# 2_FPGA.net
KiCad netlist of a schematic drawn in Altium Designer
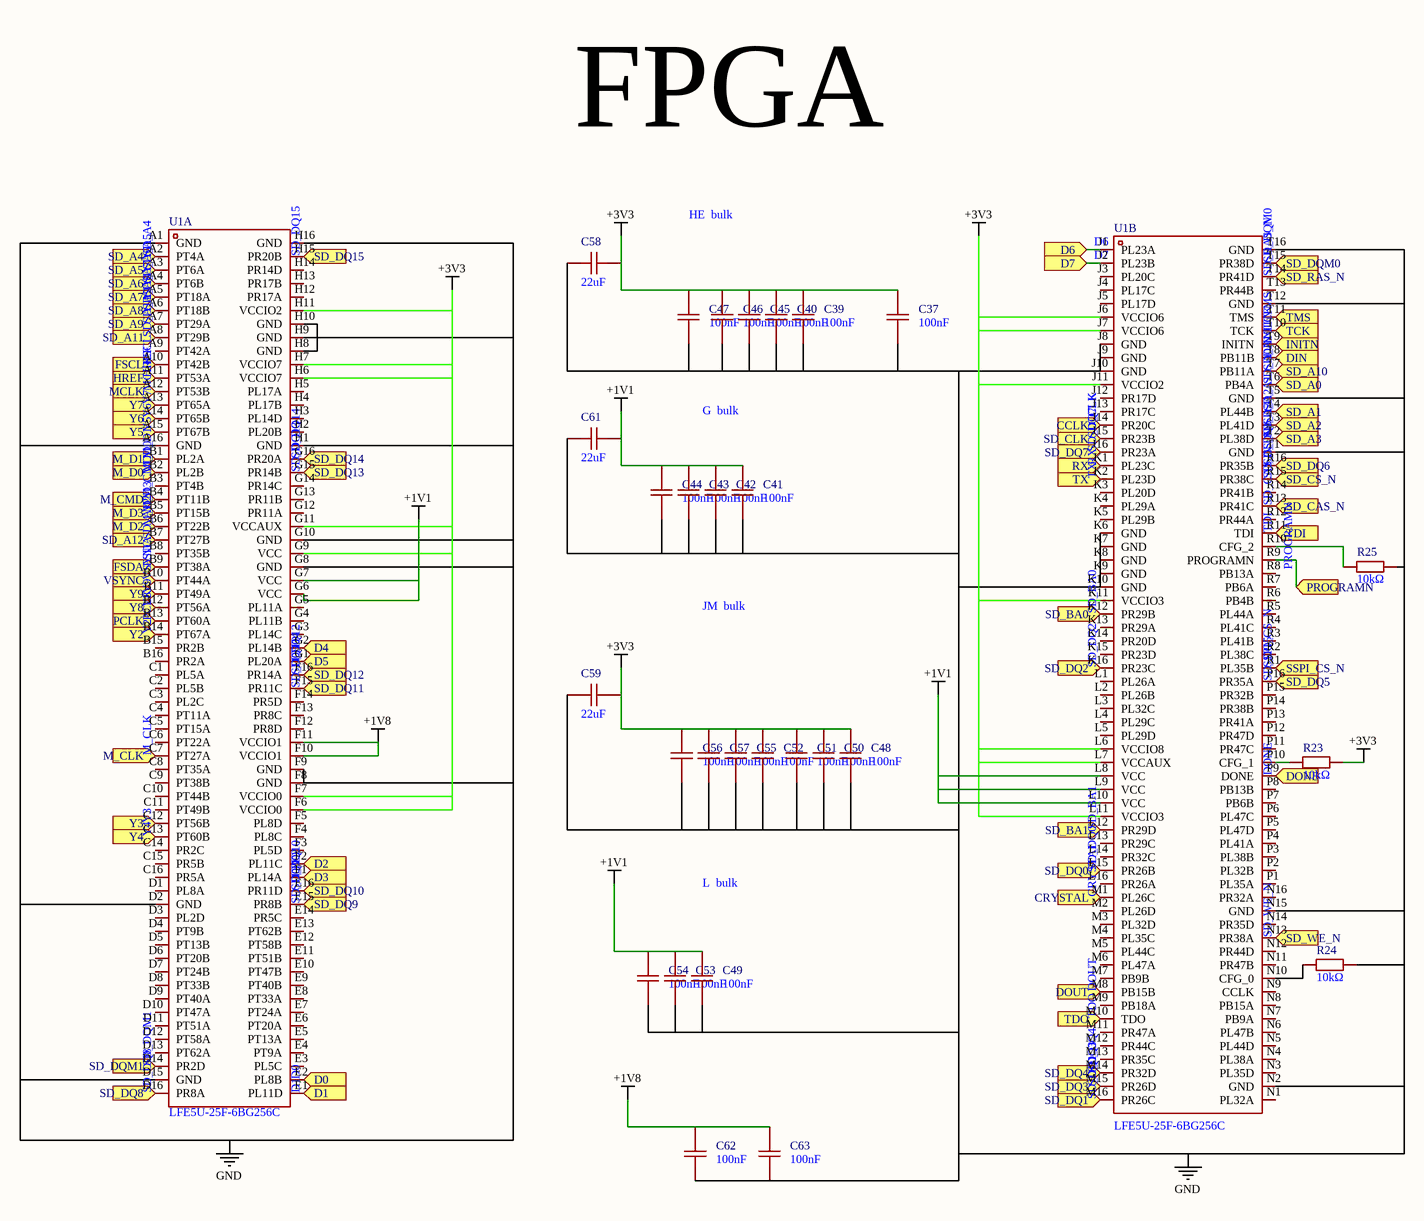
[diagram p0: 2_FPGA.schdoc]

(export (version "E")
  (design (tool "Eeschema 10.0.6"))
  (components
    (comp (ref "C37")
      (value "100nF")
      (footprint "C01005")
      (fields
        (field (name "MANUFACTURER") "muRata(村田)")
        (field (name "MANUFACTURER PART") "GRM022R60J104KE15D")
        (field (name "TOLERANCE") "±10%")
      )
      (libsource (lib "altium-import") (part "root_2_GRM022R60J104KE15D_"))
    )
    (comp (ref "C39")
      (value "100nF")
      (footprint "C01005")
      (fields
        (field (name "MANUFACTURER") "muRata(村田)")
        (field (name "MANUFACTURER PART") "GRM022R60J104KE15D")
        (field (name "TOLERANCE") "±10%")
      )
      (libsource (lib "altium-import") (part "root_2_GRM022R60J104KE15D_"))
    )
    (comp (ref "C40")
      (value "100nF")
      (footprint "C01005")
      (fields
        (field (name "MANUFACTURER") "muRata(村田)")
        (field (name "MANUFACTURER PART") "GRM022R60J104KE15D")
        (field (name "TOLERANCE") "±10%")
      )
      (libsource (lib "altium-import") (part "root_2_GRM022R60J104KE15D_"))
    )
    (comp (ref "C41")
      (value "100nF")
      (footprint "C01005")
      (fields
        (field (name "MANUFACTURER") "muRata(村田)")
        (field (name "MANUFACTURER PART") "GRM022R60J104KE15D")
        (field (name "TOLERANCE") "±10%")
      )
      (libsource (lib "altium-import") (part "root_2_GRM022R60J104KE15D_"))
    )
    (comp (ref "C42")
      (value "100nF")
      (footprint "C01005")
      (fields
        (field (name "MANUFACTURER") "muRata(村田)")
        (field (name "MANUFACTURER PART") "GRM022R60J104KE15D")
        (field (name "TOLERANCE") "±10%")
      )
      (libsource (lib "altium-import") (part "root_2_GRM022R60J104KE15D_"))
    )
    (comp (ref "C43")
      (value "100nF")
      (footprint "C01005")
      (fields
        (field (name "MANUFACTURER") "muRata(村田)")
        (field (name "MANUFACTURER PART") "GRM022R60J104KE15D")
        (field (name "TOLERANCE") "±10%")
      )
      (libsource (lib "altium-import") (part "root_2_GRM022R60J104KE15D_"))
    )
    (comp (ref "C44")
      (value "100nF")
      (footprint "C01005")
      (fields
        (field (name "MANUFACTURER") "muRata(村田)")
        (field (name "MANUFACTURER PART") "GRM022R60J104KE15D")
        (field (name "TOLERANCE") "±10%")
      )
      (libsource (lib "altium-import") (part "root_2_GRM022R60J104KE15D_"))
    )
    (comp (ref "C45")
      (value "100nF")
      (footprint "C01005")
      (fields
        (field (name "MANUFACTURER") "muRata(村田)")
        (field (name "MANUFACTURER PART") "GRM022R60J104KE15D")
        (field (name "TOLERANCE") "±10%")
      )
      (libsource (lib "altium-import") (part "root_2_GRM022R60J104KE15D_"))
    )
    (comp (ref "C46")
      (value "100nF")
      (footprint "C01005")
      (fields
        (field (name "MANUFACTURER") "muRata(村田)")
        (field (name "MANUFACTURER PART") "GRM022R60J104KE15D")
        (field (name "TOLERANCE") "±10%")
      )
      (libsource (lib "altium-import") (part "root_2_GRM022R60J104KE15D_"))
    )
    (comp (ref "C47")
      (value "100nF")
      (footprint "C01005")
      (fields
        (field (name "MANUFACTURER") "muRata(村田)")
        (field (name "MANUFACTURER PART") "GRM022R60J104KE15D")
        (field (name "TOLERANCE") "±10%")
      )
      (libsource (lib "altium-import") (part "root_2_GRM022R60J104KE15D_"))
    )
    (comp (ref "C48")
      (value "100nF")
      (footprint "C01005")
      (fields
        (field (name "MANUFACTURER") "muRata(村田)")
        (field (name "MANUFACTURER PART") "GRM022R60J104KE15D")
        (field (name "TOLERANCE") "±10%")
      )
      (libsource (lib "altium-import") (part "root_2_GRM022R60J104KE15D_"))
    )
    (comp (ref "C49")
      (value "100nF")
      (footprint "C01005")
      (fields
        (field (name "MANUFACTURER") "muRata(村田)")
        (field (name "MANUFACTURER PART") "GRM022R60J104KE15D")
        (field (name "TOLERANCE") "±10%")
      )
      (libsource (lib "altium-import") (part "root_2_GRM022R60J104KE15D_"))
    )
    (comp (ref "C50")
      (value "100nF")
      (footprint "C01005")
      (fields
        (field (name "MANUFACTURER") "muRata(村田)")
        (field (name "MANUFACTURER PART") "GRM022R60J104KE15D")
        (field (name "TOLERANCE") "±10%")
      )
      (libsource (lib "altium-import") (part "root_2_GRM022R60J104KE15D_"))
    )
    (comp (ref "C51")
      (value "100nF")
      (footprint "C01005")
      (fields
        (field (name "MANUFACTURER") "muRata(村田)")
        (field (name "MANUFACTURER PART") "GRM022R60J104KE15D")
        (field (name "TOLERANCE") "±10%")
      )
      (libsource (lib "altium-import") (part "root_2_GRM022R60J104KE15D_"))
    )
    (comp (ref "C52")
      (value "100nF")
      (footprint "C01005")
      (fields
        (field (name "MANUFACTURER") "muRata(村田)")
        (field (name "MANUFACTURER PART") "GRM022R60J104KE15D")
        (field (name "TOLERANCE") "±10%")
      )
      (libsource (lib "altium-import") (part "root_2_GRM022R60J104KE15D_"))
    )
    (comp (ref "C53")
      (value "100nF")
      (footprint "C01005")
      (fields
        (field (name "MANUFACTURER") "muRata(村田)")
        (field (name "MANUFACTURER PART") "GRM022R60J104KE15D")
        (field (name "TOLERANCE") "±10%")
      )
      (libsource (lib "altium-import") (part "root_2_GRM022R60J104KE15D_"))
    )
    (comp (ref "C54")
      (value "100nF")
      (footprint "C01005")
      (fields
        (field (name "MANUFACTURER") "muRata(村田)")
        (field (name "MANUFACTURER PART") "GRM022R60J104KE15D")
        (field (name "TOLERANCE") "±10%")
      )
      (libsource (lib "altium-import") (part "root_2_GRM022R60J104KE15D_"))
    )
    (comp (ref "C55")
      (value "100nF")
      (footprint "C01005")
      (fields
        (field (name "MANUFACTURER") "muRata(村田)")
        (field (name "MANUFACTURER PART") "GRM022R60J104KE15D")
        (field (name "TOLERANCE") "±10%")
      )
      (libsource (lib "altium-import") (part "root_2_GRM022R60J104KE15D_"))
    )
    (comp (ref "C56")
      (value "100nF")
      (footprint "C01005")
      (fields
        (field (name "MANUFACTURER") "muRata(村田)")
        (field (name "MANUFACTURER PART") "GRM022R60J104KE15D")
        (field (name "TOLERANCE") "±10%")
      )
      (libsource (lib "altium-import") (part "root_2_GRM022R60J104KE15D_"))
    )
    (comp (ref "C57")
      (value "100nF")
      (footprint "C01005")
      (fields
        (field (name "MANUFACTURER") "muRata(村田)")
        (field (name "MANUFACTURER PART") "GRM022R60J104KE15D")
        (field (name "TOLERANCE") "±10%")
      )
      (libsource (lib "altium-import") (part "root_2_GRM022R60J104KE15D_"))
    )
    (comp (ref "C58")
      (value "22uF")
      (footprint "C0603")
      (fields
        (field (name "MANUFACTURER") "CCTC(三环)")
        (field (name "MANUFACTURER PART") "TCC0603X5R226M6R3CT")
        (field (name "TOLERANCE") "±20%")
      )
      (libsource (lib "altium-import") (part "root_1_TCC0603X5R226M6R3CT_"))
    )
    (comp (ref "C59")
      (value "22uF")
      (footprint "C0603")
      (fields
        (field (name "MANUFACTURER") "CCTC(三环)")
        (field (name "MANUFACTURER PART") "TCC0603X5R226M6R3CT")
        (field (name "TOLERANCE") "±20%")
      )
      (libsource (lib "altium-import") (part "root_1_TCC0603X5R226M6R3CT_"))
    )
    (comp (ref "C61")
      (value "22uF")
      (footprint "C0603")
      (fields
        (field (name "MANUFACTURER") "CCTC(三环)")
        (field (name "MANUFACTURER PART") "TCC0603X5R226M6R3CT")
        (field (name "TOLERANCE") "±20%")
      )
      (libsource (lib "altium-import") (part "root_1_TCC0603X5R226M6R3CT_"))
    )
    (comp (ref "C62")
      (value "100nF")
      (footprint "C01005")
      (fields
        (field (name "MANUFACTURER") "muRata(村田)")
        (field (name "MANUFACTURER PART") "GRM022R60J104KE15D")
        (field (name "TOLERANCE") "±10%")
      )
      (libsource (lib "altium-import") (part "root_2_GRM022R60J104KE15D_"))
    )
    (comp (ref "C63")
      (value "100nF")
      (footprint "C01005")
      (fields
        (field (name "MANUFACTURER") "muRata(村田)")
        (field (name "MANUFACTURER PART") "GRM022R60J104KE15D")
        (field (name "TOLERANCE") "±10%")
      )
      (libsource (lib "altium-import") (part "root_2_GRM022R60J104KE15D_"))
    )
    (comp (ref "R23")
      (value "10kΩ")
      (footprint "R0402")
      (fields
        (field (name "MANUFACTURER") "UNI-ROYAL(厚声)")
        (field (name "MANUFACTURER PART") "0402WGF1002TCE")
        (field (name "TOLERANCE") "±1%")
      )
      (libsource (lib "altium-import") (part "root_2_0402WGF1002TCE_"))
    )
    (comp (ref "R24")
      (value "10kΩ")
      (footprint "R0402")
      (fields
        (field (name "MANUFACTURER") "UNI-ROYAL(厚声)")
        (field (name "MANUFACTURER PART") "0402WGF1002TCE")
        (field (name "TOLERANCE") "±1%")
      )
      (libsource (lib "altium-import") (part "root_2_0402WGF1002TCE_"))
    )
    (comp (ref "R25")
      (value "10kΩ")
      (footprint "R0402")
      (fields
        (field (name "MANUFACTURER") "UNI-ROYAL(厚声)")
        (field (name "MANUFACTURER PART") "0402WGF1002TCE")
        (field (name "TOLERANCE") "±1%")
      )
      (libsource (lib "altium-import") (part "root_2_0402WGF1002TCE_"))
    )
    (comp (ref "U1")
      (value "LFE5U-25F-6BG256C")
      (footprint "CABGA-256_L14.0-W14.0-R16-C16-P0.80-TL")
      (fields (field (name "MANUFACTURER") "LATTICE(莱迪思)"))
      (libsource (lib "altium-import") (part "root_0_LFE5U-25F-6BG256C_"))
    )
  )
  (nets
    (net (code "1") (name "+1V1") (class "Default")
      (node (ref "C41") (pin "1") (pinfunction "1_1") (pintype "passive"))
      (node (ref "C42") (pin "1") (pinfunction "1_1") (pintype "passive"))
      (node (ref "C43") (pin "1") (pinfunction "1_1") (pintype "passive"))
      (node (ref "C44") (pin "1") (pinfunction "1_1") (pintype "passive"))
      (node (ref "C49") (pin "1") (pinfunction "1_1") (pintype "passive"))
      (node (ref "C53") (pin "1") (pinfunction "1_1") (pintype "passive"))
      (node (ref "C54") (pin "1") (pinfunction "1_1") (pintype "passive"))
      (node (ref "C61") (pin "1") (pinfunction "1_1") (pintype "passive"))
      (node (ref "U1") (pin "G6") (pinfunction "VCC_G6") (pintype "passive"))
      (node (ref "U1") (pin "G7") (pinfunction "VCC_G7") (pintype "passive"))
      (node (ref "U1") (pin "L10") (pinfunction "VCC_L10") (pintype "passive"))
      (node (ref "U1") (pin "L8") (pinfunction "VCC_L8") (pintype "passive"))
      (node (ref "U1") (pin "L9") (pinfunction "VCC_L9") (pintype "passive"))
    )
    (net (code "2") (name "+1V8") (class "Default")
      (node (ref "C62") (pin "1") (pinfunction "1_1") (pintype "passive"))
      (node (ref "C63") (pin "1") (pinfunction "1_1") (pintype "passive"))
      (node (ref "U1") (pin "F10") (pinfunction "VCCIO1_F10") (pintype "passive"))
      (node (ref "U1") (pin "F11") (pinfunction "VCCIO1_F11") (pintype "passive"))
    )
    (net (code "3") (name "+3V3") (class "Default")
      (node (ref "C37") (pin "1") (pinfunction "1_1") (pintype "passive"))
      (node (ref "C39") (pin "1") (pinfunction "1_1") (pintype "passive"))
      (node (ref "C40") (pin "1") (pinfunction "1_1") (pintype "passive"))
      (node (ref "C45") (pin "1") (pinfunction "1_1") (pintype "passive"))
      (node (ref "C46") (pin "1") (pinfunction "1_1") (pintype "passive"))
      (node (ref "C47") (pin "1") (pinfunction "1_1") (pintype "passive"))
      (node (ref "C48") (pin "1") (pinfunction "1_1") (pintype "passive"))
      (node (ref "C50") (pin "1") (pinfunction "1_1") (pintype "passive"))
      (node (ref "C51") (pin "1") (pinfunction "1_1") (pintype "passive"))
      (node (ref "C52") (pin "1") (pinfunction "1_1") (pintype "passive"))
      (node (ref "C55") (pin "1") (pinfunction "1_1") (pintype "passive"))
      (node (ref "C56") (pin "1") (pinfunction "1_1") (pintype "passive"))
      (node (ref "C57") (pin "1") (pinfunction "1_1") (pintype "passive"))
      (node (ref "C58") (pin "1") (pinfunction "1_1") (pintype "passive"))
      (node (ref "C59") (pin "1") (pinfunction "1_1") (pintype "passive"))
      (node (ref "R23") (pin "1") (pinfunction "1_1") (pintype "passive"))
      (node (ref "U1") (pin "F6") (pinfunction "VCCIO0_F6") (pintype "passive"))
      (node (ref "U1") (pin "F7") (pinfunction "VCCIO0_F7") (pintype "passive"))
      (node (ref "U1") (pin "G11") (pinfunction "VCCAUX_G11") (pintype "passive"))
      (node (ref "U1") (pin "G9") (pinfunction "VCC_G9") (pintype "passive"))
      (node (ref "U1") (pin "H11") (pinfunction "VCCIO2_H11") (pintype "passive"))
      (node (ref "U1") (pin "H6") (pinfunction "VCCIO7_H6") (pintype "passive"))
      (node (ref "U1") (pin "H7") (pinfunction "VCCIO7_H7") (pintype "passive"))
      (node (ref "U1") (pin "J11") (pinfunction "VCCIO2_J11") (pintype "passive"))
      (node (ref "U1") (pin "J6") (pinfunction "VCCIO6_J6") (pintype "passive"))
      (node (ref "U1") (pin "J7") (pinfunction "VCCIO6_J7") (pintype "passive"))
      (node (ref "U1") (pin "K11") (pinfunction "VCCIO3_K11") (pintype "passive"))
      (node (ref "U1") (pin "L11") (pinfunction "VCCIO3_L11") (pintype "passive"))
      (node (ref "U1") (pin "L6") (pinfunction "VCCIO8_L6") (pintype "passive"))
      (node (ref "U1") (pin "L7") (pinfunction "VCCAUX_L7") (pintype "passive"))
    )
    (net (code "4") (name "/CCLK") (class "Default")
      (node (ref "U1") (pin "J14") (pinfunction "PR20C_J14") (pintype "passive"))
    )
    (net (code "5") (name "/CRYSTAL") (class "Default")
      (node (ref "U1") (pin "M1") (pinfunction "PL26C_M1") (pintype "passive"))
    )
    (net (code "6") (name "/D0") (class "Default")
      (node (ref "U1") (pin "E2") (pinfunction "PL8B_E2") (pintype "passive"))
    )
    (net (code "7") (name "/D1") (class "Default")
      (node (ref "U1") (pin "E1") (pinfunction "PL11D_E1") (pintype "passive"))
    )
    (net (code "8") (name "/D2") (class "Default")
      (node (ref "U1") (pin "F2") (pinfunction "PL11C_F2") (pintype "passive"))
    )
    (net (code "9") (name "/D3") (class "Default")
      (node (ref "U1") (pin "F1") (pinfunction "PL14A_F1") (pintype "passive"))
    )
    (net (code "10") (name "/D4") (class "Default")
      (node (ref "U1") (pin "G2") (pinfunction "PL14B_G2") (pintype "passive"))
    )
    (net (code "11") (name "/D5") (class "Default")
      (node (ref "U1") (pin "G1") (pinfunction "PL20A_G1") (pintype "passive"))
    )
    (net (code "12") (name "/D6") (class "Default")
      (node (ref "U1") (pin "J1") (pinfunction "PL23A_J1") (pintype "passive"))
    )
    (net (code "13") (name "/D7") (class "Default")
      (node (ref "U1") (pin "J2") (pinfunction "PL23B_J2") (pintype "passive"))
    )
    (net (code "14") (name "/DIN") (class "Default")
      (node (ref "U1") (pin "T8") (pinfunction "PB11B_T8") (pintype "passive"))
    )
    (net (code "15") (name "/DONE") (class "Default")
      (node (ref "U1") (pin "P9") (pinfunction "DONE_P9") (pintype "passive"))
    )
    (net (code "16") (name "/DOUT") (class "Default")
      (node (ref "U1") (pin "M8") (pinfunction "PB15B_M8") (pintype "passive"))
    )
    (net (code "17") (name "/FSCL") (class "Default")
      (node (ref "U1") (pin "A10") (pinfunction "PT42B_A10") (pintype "passive"))
    )
    (net (code "18") (name "/FSDA") (class "Default")
      (node (ref "U1") (pin "B9") (pinfunction "PT38A_B9") (pintype "passive"))
    )
    (net (code "19") (name "/HREF") (class "Default")
      (node (ref "U1") (pin "A11") (pinfunction "PT53A_A11") (pintype "passive"))
    )
    (net (code "20") (name "/INITN") (class "Default")
      (node (ref "U1") (pin "T9") (pinfunction "INITN_T9") (pintype "passive"))
    )
    (net (code "21") (name "/MCLK") (class "Default")
      (node (ref "U1") (pin "A12") (pinfunction "PT53B_A12") (pintype "passive"))
    )
    (net (code "22") (name "/M_CLK") (class "Default")
      (node (ref "U1") (pin "C7") (pinfunction "PT27A_C7") (pintype "passive"))
    )
    (net (code "23") (name "/M_CMD") (class "Default")
      (node (ref "U1") (pin "B4") (pinfunction "PT11B_B4") (pintype "passive"))
    )
    (net (code "24") (name "/M_D0") (class "Default")
      (node (ref "U1") (pin "B2") (pinfunction "PL2B_B2") (pintype "passive"))
    )
    (net (code "25") (name "/M_D1") (class "Default")
      (node (ref "U1") (pin "B1") (pinfunction "PL2A_B1") (pintype "passive"))
    )
    (net (code "26") (name "/M_D2") (class "Default")
      (node (ref "U1") (pin "B6") (pinfunction "PT22B_B6") (pintype "passive"))
    )
    (net (code "27") (name "/M_D3") (class "Default")
      (node (ref "U1") (pin "B5") (pinfunction "PT15B_B5") (pintype "passive"))
    )
    (net (code "28") (name "/PCLK") (class "Default")
      (node (ref "U1") (pin "B13") (pinfunction "PT60A_B13") (pintype "passive"))
    )
    (net (code "29") (name "/PROGRAMN") (class "Default")
      (node (ref "U1") (pin "R9") (pinfunction "PROGRAMN_R9") (pintype "passive"))
    )
    (net (code "30") (name "/RX") (class "Default")
      (node (ref "U1") (pin "K1") (pinfunction "PL23C_K1") (pintype "passive"))
    )
    (net (code "31") (name "/SD_A0") (class "Default")
      (node (ref "U1") (pin "T6") (pinfunction "PB4A_T6") (pintype "passive"))
    )
    (net (code "32") (name "/SD_A1") (class "Default")
      (node (ref "U1") (pin "T4") (pinfunction "PL44B_T4") (pintype "passive"))
    )
    (net (code "33") (name "/SD_A2") (class "Default")
      (node (ref "U1") (pin "T3") (pinfunction "PL41D_T3") (pintype "passive"))
    )
    (net (code "34") (name "/SD_A3") (class "Default")
      (node (ref "U1") (pin "T2") (pinfunction "PL38D_T2") (pintype "passive"))
    )
    (net (code "35") (name "/SD_A4") (class "Default")
      (node (ref "U1") (pin "A2") (pinfunction "PT4A_A2") (pintype "passive"))
    )
    (net (code "36") (name "/SD_A5") (class "Default")
      (node (ref "U1") (pin "A3") (pinfunction "PT6A_A3") (pintype "passive"))
    )
    (net (code "37") (name "/SD_A6") (class "Default")
      (node (ref "U1") (pin "A4") (pinfunction "PT6B_A4") (pintype "passive"))
    )
    (net (code "38") (name "/SD_A7") (class "Default")
      (node (ref "U1") (pin "A5") (pinfunction "PT18A_A5") (pintype "passive"))
    )
    (net (code "39") (name "/SD_A8") (class "Default")
      (node (ref "U1") (pin "A6") (pinfunction "PT18B_A6") (pintype "passive"))
    )
    (net (code "40") (name "/SD_A9") (class "Default")
      (node (ref "U1") (pin "A7") (pinfunction "PT29A_A7") (pintype "passive"))
    )
    (net (code "41") (name "/SD_A10") (class "Default")
      (node (ref "U1") (pin "T7") (pinfunction "PB11A_T7") (pintype "passive"))
    )
    (net (code "42") (name "/SD_A11") (class "Default")
      (node (ref "U1") (pin "A8") (pinfunction "PT29B_A8") (pintype "passive"))
    )
    (net (code "43") (name "/SD_A12") (class "Default")
      (node (ref "U1") (pin "B7") (pinfunction "PT27B_B7") (pintype "passive"))
    )
    (net (code "44") (name "/SD_BA0") (class "Default")
      (node (ref "U1") (pin "K12") (pinfunction "PR29B_K12") (pintype "passive"))
    )
    (net (code "45") (name "/SD_BA1") (class "Default")
      (node (ref "U1") (pin "L12") (pinfunction "PR29D_L12") (pintype "passive"))
    )
    (net (code "46") (name "/SD_CAS_N") (class "Default")
      (node (ref "U1") (pin "R13") (pinfunction "PR41C_R13") (pintype "passive"))
    )
    (net (code "47") (name "/SD_CLK") (class "Default")
      (node (ref "U1") (pin "J15") (pinfunction "PR23B_J15") (pintype "passive"))
    )
    (net (code "48") (name "/SD_CS_N") (class "Default")
      (node (ref "U1") (pin "R15") (pinfunction "PR38C_R15") (pintype "passive"))
    )
    (net (code "49") (name "/SD_DQ0") (class "Default")
      (node (ref "U1") (pin "L15") (pinfunction "PR26B_L15") (pintype "passive"))
    )
    (net (code "50") (name "/SD_DQ1") (class "Default")
      (node (ref "U1") (pin "M16") (pinfunction "PR26C_M16") (pintype "passive"))
    )
    (net (code "51") (name "/SD_DQ2") (class "Default")
      (node (ref "U1") (pin "K16") (pinfunction "PR23C_K16") (pintype "passive"))
    )
    (net (code "52") (name "/SD_DQ3") (class "Default")
      (node (ref "U1") (pin "M15") (pinfunction "PR26D_M15") (pintype "passive"))
    )
    (net (code "53") (name "/SD_DQ4") (class "Default")
      (node (ref "U1") (pin "M14") (pinfunction "PR32D_M14") (pintype "passive"))
    )
    (net (code "54") (name "/SD_DQ5") (class "Default")
      (node (ref "U1") (pin "P16") (pinfunction "PR35A_P16") (pintype "passive"))
    )
    (net (code "55") (name "/SD_DQ6") (class "Default")
      (node (ref "U1") (pin "R16") (pinfunction "PR35B_R16") (pintype "passive"))
    )
    (net (code "56") (name "/SD_DQ7") (class "Default")
      (node (ref "U1") (pin "J16") (pinfunction "PR23A_J16") (pintype "passive"))
    )
    (net (code "57") (name "/SD_DQ8") (class "Default")
      (node (ref "U1") (pin "D16") (pinfunction "PR8A_D16") (pintype "passive"))
    )
    (net (code "58") (name "/SD_DQ9") (class "Default")
      (node (ref "U1") (pin "E15") (pinfunction "PR8B_E15") (pintype "passive"))
    )
    (net (code "59") (name "/SD_DQ10") (class "Default")
      (node (ref "U1") (pin "E16") (pinfunction "PR11D_E16") (pintype "passive"))
    )
    (net (code "60") (name "/SD_DQ11") (class "Default")
      (node (ref "U1") (pin "F15") (pinfunction "PR11C_F15") (pintype "passive"))
    )
    (net (code "61") (name "/SD_DQ12") (class "Default")
      (node (ref "U1") (pin "F16") (pinfunction "PR14A_F16") (pintype "passive"))
    )
    (net (code "62") (name "/SD_DQ13") (class "Default")
      (node (ref "U1") (pin "G15") (pinfunction "PR14B_G15") (pintype "passive"))
    )
    (net (code "63") (name "/SD_DQ14") (class "Default")
      (node (ref "U1") (pin "G16") (pinfunction "PR20A_G16") (pintype "passive"))
    )
    (net (code "64") (name "/SD_DQ15") (class "Default")
      (node (ref "U1") (pin "H15") (pinfunction "PR20B_H15") (pintype "passive"))
    )
    (net (code "65") (name "/SD_DQM0") (class "Default")
      (node (ref "U1") (pin "T15") (pinfunction "PR38D_T15") (pintype "passive"))
    )
    (net (code "66") (name "/SD_DQM1") (class "Default")
      (node (ref "U1") (pin "D14") (pinfunction "PR2D_D14") (pintype "passive"))
    )
    (net (code "67") (name "/SD_RAS_N") (class "Default")
      (node (ref "U1") (pin "T14") (pinfunction "PR41D_T14") (pintype "passive"))
    )
    (net (code "68") (name "/SD_WE_N") (class "Default")
      (node (ref "U1") (pin "N13") (pinfunction "PR38A_N13") (pintype "passive"))
    )
    (net (code "69") (name "/SSPI_CS_N") (class "Default")
      (node (ref "U1") (pin "R1") (pinfunction "PL35B_R1") (pintype "passive"))
    )
    (net (code "70") (name "/TCK") (class "Default")
      (node (ref "U1") (pin "T10") (pinfunction "TCK_T10") (pintype "passive"))
    )
    (net (code "71") (name "/TDI") (class "Default")
      (node (ref "U1") (pin "R11") (pinfunction "TDI_R11") (pintype "passive"))
    )
    (net (code "72") (name "/TDO") (class "Default")
      (node (ref "U1") (pin "M10") (pinfunction "TDO_M10") (pintype "passive"))
    )
    (net (code "73") (name "/TMS") (class "Default")
      (node (ref "U1") (pin "T11") (pinfunction "TMS_T11") (pintype "passive"))
    )
    (net (code "74") (name "/TX") (class "Default")
      (node (ref "U1") (pin "K2") (pinfunction "PL23D_K2") (pintype "passive"))
    )
    (net (code "75") (name "/VSYNC") (class "Default")
      (node (ref "U1") (pin "B10") (pinfunction "PT44A_B10") (pintype "passive"))
    )
    (net (code "76") (name "/Y2") (class "Default")
      (node (ref "U1") (pin "B14") (pinfunction "PT67A_B14") (pintype "passive"))
    )
    (net (code "77") (name "/Y3") (class "Default")
      (node (ref "U1") (pin "C12") (pinfunction "PT56B_C12") (pintype "passive"))
    )
    (net (code "78") (name "/Y4") (class "Default")
      (node (ref "U1") (pin "C13") (pinfunction "PT60B_C13") (pintype "passive"))
    )
    (net (code "79") (name "/Y5") (class "Default")
      (node (ref "U1") (pin "A15") (pinfunction "PT67B_A15") (pintype "passive"))
    )
    (net (code "80") (name "/Y6") (class "Default")
      (node (ref "U1") (pin "A14") (pinfunction "PT65B_A14") (pintype "passive"))
    )
    (net (code "81") (name "/Y7") (class "Default")
      (node (ref "U1") (pin "A13") (pinfunction "PT65A_A13") (pintype "passive"))
    )
    (net (code "82") (name "/Y8") (class "Default")
      (node (ref "U1") (pin "B12") (pinfunction "PT56A_B12") (pintype "passive"))
    )
    (net (code "83") (name "/Y9") (class "Default")
      (node (ref "U1") (pin "B11") (pinfunction "PT49A_B11") (pintype "passive"))
    )
    (net (code "84") (name "GND") (class "Default")
      (node (ref "C37") (pin "2") (pinfunction "2_2") (pintype "passive"))
      (node (ref "C39") (pin "2") (pinfunction "2_2") (pintype "passive"))
      (node (ref "C40") (pin "2") (pinfunction "2_2") (pintype "passive"))
      (node (ref "C41") (pin "2") (pinfunction "2_2") (pintype "passive"))
      (node (ref "C42") (pin "2") (pinfunction "2_2") (pintype "passive"))
      (node (ref "C43") (pin "2") (pinfunction "2_2") (pintype "passive"))
      (node (ref "C44") (pin "2") (pinfunction "2_2") (pintype "passive"))
      (node (ref "C45") (pin "2") (pinfunction "2_2") (pintype "passive"))
      (node (ref "C46") (pin "2") (pinfunction "2_2") (pintype "passive"))
      (node (ref "C47") (pin "2") (pinfunction "2_2") (pintype "passive"))
      (node (ref "C48") (pin "2") (pinfunction "2_2") (pintype "passive"))
      (node (ref "C49") (pin "2") (pinfunction "2_2") (pintype "passive"))
      (node (ref "C50") (pin "2") (pinfunction "2_2") (pintype "passive"))
      (node (ref "C51") (pin "2") (pinfunction "2_2") (pintype "passive"))
      (node (ref "C52") (pin "2") (pinfunction "2_2") (pintype "passive"))
      (node (ref "C53") (pin "2") (pinfunction "2_2") (pintype "passive"))
      (node (ref "C54") (pin "2") (pinfunction "2_2") (pintype "passive"))
      (node (ref "C55") (pin "2") (pinfunction "2_2") (pintype "passive"))
      (node (ref "C56") (pin "2") (pinfunction "2_2") (pintype "passive"))
      (node (ref "C57") (pin "2") (pinfunction "2_2") (pintype "passive"))
      (node (ref "C58") (pin "2") (pinfunction "2_2") (pintype "passive"))
      (node (ref "C59") (pin "2") (pinfunction "2_2") (pintype "passive"))
      (node (ref "C61") (pin "2") (pinfunction "2_2") (pintype "passive"))
      (node (ref "C62") (pin "2") (pinfunction "2_2") (pintype "passive"))
      (node (ref "C63") (pin "2") (pinfunction "2_2") (pintype "passive"))
      (node (ref "R24") (pin "1") (pinfunction "1_1") (pintype "passive"))
      (node (ref "R25") (pin "1") (pinfunction "1_1") (pintype "passive"))
      (node (ref "U1") (pin "A1") (pinfunction "GND_A1") (pintype "passive"))
      (node (ref "U1") (pin "A16") (pinfunction "GND_A16") (pintype "passive"))
      (node (ref "U1") (pin "D15") (pinfunction "GND_D15") (pintype "passive"))
      (node (ref "U1") (pin "D2") (pinfunction "GND_D2") (pintype "passive"))
      (node (ref "U1") (pin "F8") (pinfunction "GND_F8") (pintype "passive"))
      (node (ref "U1") (pin "F9") (pinfunction "GND_F9") (pintype "passive"))
      (node (ref "U1") (pin "G10") (pinfunction "GND_G10") (pintype "passive"))
      (node (ref "U1") (pin "G8") (pinfunction "GND_G8") (pintype "passive"))
      (node (ref "U1") (pin "H1") (pinfunction "GND_H1") (pintype "passive"))
      (node (ref "U1") (pin "H10") (pinfunction "GND_H10") (pintype "passive"))
      (node (ref "U1") (pin "H16") (pinfunction "GND_H16") (pintype "passive"))
      (node (ref "U1") (pin "H8") (pinfunction "GND_H8") (pintype "passive"))
      (node (ref "U1") (pin "H9") (pinfunction "GND_H9") (pintype "passive"))
      (node (ref "U1") (pin "J10") (pinfunction "GND_J10") (pintype "passive"))
      (node (ref "U1") (pin "J8") (pinfunction "GND_J8") (pintype "passive"))
      (node (ref "U1") (pin "J9") (pinfunction "GND_J9") (pintype "passive"))
      (node (ref "U1") (pin "K10") (pinfunction "GND_K10") (pintype "passive"))
      (node (ref "U1") (pin "K6") (pinfunction "GND_K6") (pintype "passive"))
      (node (ref "U1") (pin "K7") (pinfunction "GND_K7") (pintype "passive"))
      (node (ref "U1") (pin "K8") (pinfunction "GND_K8") (pintype "passive"))
      (node (ref "U1") (pin "K9") (pinfunction "GND_K9") (pintype "passive"))
      (node (ref "U1") (pin "N15") (pinfunction "GND_N15") (pintype "passive"))
      (node (ref "U1") (pin "N2") (pinfunction "GND_N2") (pintype "passive"))
      (node (ref "U1") (pin "T1") (pinfunction "GND_T1") (pintype "passive"))
      (node (ref "U1") (pin "T12") (pinfunction "GND_T12") (pintype "passive"))
      (node (ref "U1") (pin "T16") (pinfunction "GND_T16") (pintype "passive"))
      (node (ref "U1") (pin "T5") (pinfunction "GND_T5") (pintype "passive"))
    )
    (net (code "85") (name "Net-(U1B-CFG_0)") (class "Default")
      (node (ref "R24") (pin "2") (pinfunction "2_2") (pintype "passive"))
      (node (ref "U1") (pin "N10") (pinfunction "CFG_0_N10") (pintype "passive"))
    )
    (net (code "86") (name "Net-(U1B-CFG_1)") (class "Default")
      (node (ref "R23") (pin "2") (pinfunction "2_2") (pintype "passive"))
      (node (ref "U1") (pin "P10") (pinfunction "CFG_1_P10") (pintype "passive"))
    )
    (net (code "87") (name "Net-(U1B-CFG_2)") (class "Default")
      (node (ref "R25") (pin "2") (pinfunction "2_2") (pintype "passive"))
      (node (ref "U1") (pin "R10") (pinfunction "CFG_2_R10") (pintype "passive"))
    )
    (net (code "88") (name "unconnected-(U1A-PL2C-PadC3)") (class "Default")
      (node (ref "U1") (pin "C3") (pinfunction "PL2C_C3") (pintype "passive"))
    )
    (net (code "89") (name "unconnected-(U1A-PL2D-PadD3)") (class "Default")
      (node (ref "U1") (pin "D3") (pinfunction "PL2D_D3") (pintype "passive"))
    )
    (net (code "90") (name "unconnected-(U1A-PL5A-PadC1)") (class "Default")
      (node (ref "U1") (pin "C1") (pinfunction "PL5A_C1") (pintype "passive"))
    )
    (net (code "91") (name "unconnected-(U1A-PL5B-PadC2)") (class "Default")
      (node (ref "U1") (pin "C2") (pinfunction "PL5B_C2") (pintype "passive"))
    )
    (net (code "92") (name "unconnected-(U1A-PL5C-PadE3)") (class "Default")
      (node (ref "U1") (pin "E3") (pinfunction "PL5C_E3") (pintype "passive"))
    )
    (net (code "93") (name "unconnected-(U1A-PL5D-PadF3)") (class "Default")
      (node (ref "U1") (pin "F3") (pinfunction "PL5D_F3") (pintype "passive"))
    )
    (net (code "94") (name "unconnected-(U1A-PL8A-PadD1)") (class "Default")
      (node (ref "U1") (pin "D1") (pinfunction "PL8A_D1") (pintype "passive"))
    )
    (net (code "95") (name "unconnected-(U1A-PL8C-PadF4)") (class "Default")
      (node (ref "U1") (pin "F4") (pinfunction "PL8C_F4") (pintype "passive"))
    )
    (net (code "96") (name "unconnected-(U1A-PL8D-PadF5)") (class "Default")
      (node (ref "U1") (pin "F5") (pinfunction "PL8D_F5") (pintype "passive"))
    )
    (net (code "97") (name "unconnected-(U1A-PL11A-PadG5)") (class "Default")
      (node (ref "U1") (pin "G5") (pinfunction "PL11A_G5") (pintype "passive"))
    )
    (net (code "98") (name "unconnected-(U1A-PL11B-PadG4)") (class "Default")
      (node (ref "U1") (pin "G4") (pinfunction "PL11B_G4") (pintype "passive"))
    )
    (net (code "99") (name "unconnected-(U1A-PL14C-PadG3)") (class "Default")
      (node (ref "U1") (pin "G3") (pinfunction "PL14C_G3") (pintype "passive"))
    )
    (net (code "100") (name "unconnected-(U1A-PL14D-PadH3)") (class "Default")
      (node (ref "U1") (pin "H3") (pinfunction "PL14D_H3") (pintype "passive"))
    )
    (net (code "101") (name "unconnected-(U1A-PL17A-PadH5)") (class "Default")
      (node (ref "U1") (pin "H5") (pinfunction "PL17A_H5") (pintype "passive"))
    )
    (net (code "102") (name "unconnected-(U1A-PL17B-PadH4)") (class "Default")
      (node (ref "U1") (pin "H4") (pinfunction "PL17B_H4") (pintype "passive"))
    )
    (net (code "103") (name "unconnected-(U1A-PL20B-PadH2)") (class "Default")
      (node (ref "U1") (pin "H2") (pinfunction "PL20B_H2") (pintype "passive"))
    )
    (net (code "104") (name "unconnected-(U1A-PR2A-PadB16)") (class "Default")
      (node (ref "U1") (pin "B16") (pinfunction "PR2A_B16") (pintype "passive"))
    )
    (net (code "105") (name "unconnected-(U1A-PR2B-PadB15)") (class "Default")
      (node (ref "U1") (pin "B15") (pinfunction "PR2B_B15") (pintype "passive"))
    )
    (net (code "106") (name "unconnected-(U1A-PR2C-PadC14)") (class "Default")
      (node (ref "U1") (pin "C14") (pinfunction "PR2C_C14") (pintype "passive"))
    )
    (net (code "107") (name "unconnected-(U1A-PR5A-PadC16)") (class "Default")
      (node (ref "U1") (pin "C16") (pinfunction "PR5A_C16") (pintype "passive"))
    )
    (net (code "108") (name "unconnected-(U1A-PR5B-PadC15)") (class "Default")
      (node (ref "U1") (pin "C15") (pinfunction "PR5B_C15") (pintype "passive"))
    )
    (net (code "109") (name "unconnected-(U1A-PR5C-PadE14)") (class "Default")
      (node (ref "U1") (pin "E14") (pinfunction "PR5C_E14") (pintype "passive"))
    )
    (net (code "110") (name "unconnected-(U1A-PR5D-PadF14)") (class "Default")
      (node (ref "U1") (pin "F14") (pinfunction "PR5D_F14") (pintype "passive"))
    )
    (net (code "111") (name "unconnected-(U1A-PR8C-PadF13)") (class "Default")
      (node (ref "U1") (pin "F13") (pinfunction "PR8C_F13") (pintype "passive"))
    )
    (net (code "112") (name "unconnected-(U1A-PR8D-PadF12)") (class "Default")
      (node (ref "U1") (pin "F12") (pinfunction "PR8D_F12") (pintype "passive"))
    )
    (net (code "113") (name "unconnected-(U1A-PR11A-PadG12)") (class "Default")
      (node (ref "U1") (pin "G12") (pinfunction "PR11A_G12") (pintype "passive"))
    )
    (net (code "114") (name "unconnected-(U1A-PR11B-PadG13)") (class "Default")
      (node (ref "U1") (pin "G13") (pinfunction "PR11B_G13") (pintype "passive"))
    )
    (net (code "115") (name "unconnected-(U1A-PR14C-PadG14)") (class "Default")
      (node (ref "U1") (pin "G14") (pinfunction "PR14C_G14") (pintype "passive"))
    )
    (net (code "116") (name "unconnected-(U1A-PR14D-PadH14)") (class "Default")
      (node (ref "U1") (pin "H14") (pinfunction "PR14D_H14") (pintype "passive"))
    )
    (net (code "117") (name "unconnected-(U1A-PR17A-PadH12)") (class "Default")
      (node (ref "U1") (pin "H12") (pinfunction "PR17A_H12") (pintype "passive"))
    )
    (net (code "118") (name "unconnected-(U1A-PR17B-PadH13)") (class "Default")
      (node (ref "U1") (pin "H13") (pinfunction "PR17B_H13") (pintype "passive"))
    )
    (net (code "119") (name "unconnected-(U1A-PT4B-PadB3)") (class "Default")
      (node (ref "U1") (pin "B3") (pinfunction "PT4B_B3") (pintype "passive"))
    )
    (net (code "120") (name "unconnected-(U1A-PT9A-PadE4)") (class "Default")
      (node (ref "U1") (pin "E4") (pinfunction "PT9A_E4") (pintype "passive"))
    )
    (net (code "121") (name "unconnected-(U1A-PT9B-PadD4)") (class "Default")
      (node (ref "U1") (pin "D4") (pinfunction "PT9B_D4") (pintype "passive"))
    )
    (net (code "122") (name "unconnected-(U1A-PT11A-PadC4)") (class "Default")
      (node (ref "U1") (pin "C4") (pinfunction "PT11A_C4") (pintype "passive"))
    )
    (net (code "123") (name "unconnected-(U1A-PT13A-PadE5)") (class "Default")
      (node (ref "U1") (pin "E5") (pinfunction "PT13A_E5") (pintype "passive"))
    )
    (net (code "124") (name "unconnected-(U1A-PT13B-PadD5)") (class "Default")
      (node (ref "U1") (pin "D5") (pinfunction "PT13B_D5") (pintype "passive"))
    )
    (net (code "125") (name "unconnected-(U1A-PT15A-PadC5)") (class "Default")
      (node (ref "U1") (pin "C5") (pinfunction "PT15A_C5") (pintype "passive"))
    )
    (net (code "126") (name "unconnected-(U1A-PT20A-PadE6)") (class "Default")
      (node (ref "U1") (pin "E6") (pinfunction "PT20A_E6") (pintype "passive"))
    )
    (net (code "127") (name "unconnected-(U1A-PT20B-PadD6)") (class "Default")
      (node (ref "U1") (pin "D6") (pinfunction "PT20B_D6") (pintype "passive"))
    )
    (net (code "128") (name "unconnected-(U1A-PT22A-PadC6)") (class "Default")
      (node (ref "U1") (pin "C6") (pinfunction "PT22A_C6") (pintype "passive"))
    )
    (net (code "129") (name "unconnected-(U1A-PT24A-PadE7)") (class "Default")
      (node (ref "U1") (pin "E7") (pinfunction "PT24A_E7") (pintype "passive"))
    )
    (net (code "130") (name "unconnected-(U1A-PT24B-PadD7)") (class "Default")
      (node (ref "U1") (pin "D7") (pinfunction "PT24B_D7") (pintype "passive"))
    )
    (net (code "131") (name "unconnected-(U1A-PT33A-PadE8)") (class "Default")
      (node (ref "U1") (pin "E8") (pinfunction "PT33A_E8") (pintype "passive"))
    )
    (net (code "132") (name "unconnected-(U1A-PT33B-PadD8)") (class "Default")
      (node (ref "U1") (pin "D8") (pinfunction "PT33B_D8") (pintype "passive"))
    )
    (net (code "133") (name "unconnected-(U1A-PT35A-PadC8)") (class "Default")
      (node (ref "U1") (pin "C8") (pinfunction "PT35A_C8") (pintype "passive"))
    )
    (net (code "134") (name "unconnected-(U1A-PT35B-PadB8)") (class "Default")
      (node (ref "U1") (pin "B8") (pinfunction "PT35B_B8") (pintype "passive"))
    )
    (net (code "135") (name "unconnected-(U1A-PT38B-PadC9)") (class "Default")
      (node (ref "U1") (pin "C9") (pinfunction "PT38B_C9") (pintype "passive"))
    )
    (net (code "136") (name "unconnected-(U1A-PT40A-PadD9)") (class "Default")
      (node (ref "U1") (pin "D9") (pinfunction "PT40A_D9") (pintype "passive"))
    )
    (net (code "137") (name "unconnected-(U1A-PT40B-PadE9)") (class "Default")
      (node (ref "U1") (pin "E9") (pinfunction "PT40B_E9") (pintype "passive"))
    )
    (net (code "138") (name "unconnected-(U1A-PT42A-PadA9)") (class "Default")
      (node (ref "U1") (pin "A9") (pinfunction "PT42A_A9") (pintype "passive"))
    )
    (net (code "139") (name "unconnected-(U1A-PT44B-PadC10)") (class "Default")
      (node (ref "U1") (pin "C10") (pinfunction "PT44B_C10") (pintype "passive"))
    )
    (net (code "140") (name "unconnected-(U1A-PT47A-PadD10)") (class "Default")
      (node (ref "U1") (pin "D10") (pinfunction "PT47A_D10") (pintype "passive"))
    )
    (net (code "141") (name "unconnected-(U1A-PT47B-PadE10)") (class "Default")
      (node (ref "U1") (pin "E10") (pinfunction "PT47B_E10") (pintype "passive"))
    )
    (net (code "142") (name "unconnected-(U1A-PT49B-PadC11)") (class "Default")
      (node (ref "U1") (pin "C11") (pinfunction "PT49B_C11") (pintype "passive"))
    )
    (net (code "143") (name "unconnected-(U1A-PT51A-PadD11)") (class "Default")
      (node (ref "U1") (pin "D11") (pinfunction "PT51A_D11") (pintype "passive"))
    )
    (net (code "144") (name "unconnected-(U1A-PT51B-PadE11)") (class "Default")
      (node (ref "U1") (pin "E11") (pinfunction "PT51B_E11") (pintype "passive"))
    )
    (net (code "145") (name "unconnected-(U1A-PT58A-PadD12)") (class "Default")
      (node (ref "U1") (pin "D12") (pinfunction "PT58A_D12") (pintype "passive"))
    )
    (net (code "146") (name "unconnected-(U1A-PT58B-PadE12)") (class "Default")
      (node (ref "U1") (pin "E12") (pinfunction "PT58B_E12") (pintype "passive"))
    )
    (net (code "147") (name "unconnected-(U1A-PT62A-PadD13)") (class "Default")
      (node (ref "U1") (pin "D13") (pinfunction "PT62A_D13") (pintype "passive"))
    )
    (net (code "148") (name "unconnected-(U1A-PT62B-PadE13)") (class "Default")
      (node (ref "U1") (pin "E13") (pinfunction "PT62B_E13") (pintype "passive"))
    )
    (net (code "149") (name "unconnected-(U1B-CCLK-PadN9)") (class "Default")
      (node (ref "U1") (pin "N9") (pinfunction "CCLK_N9") (pintype "passive"))
    )
    (net (code "150") (name "unconnected-(U1B-PB4B-PadR6)") (class "Default")
      (node (ref "U1") (pin "R6") (pinfunction "PB4B_R6") (pintype "passive"))
    )
    (net (code "151") (name "unconnected-(U1B-PB6A-PadR7)") (class "Default")
      (node (ref "U1") (pin "R7") (pinfunction "PB6A_R7") (pintype "passive"))
    )
    (net (code "152") (name "unconnected-(U1B-PB6B-PadP7)") (class "Default")
      (node (ref "U1") (pin "P7") (pinfunction "PB6B_P7") (pintype "passive"))
    )
    (net (code "153") (name "unconnected-(U1B-PB9A-PadN7)") (class "Default")
      (node (ref "U1") (pin "N7") (pinfunction "PB9A_N7") (pintype "passive"))
    )
    (net (code "154") (name "unconnected-(U1B-PB9B-PadM7)") (class "Default")
      (node (ref "U1") (pin "M7") (pinfunction "PB9B_M7") (pintype "passive"))
    )
    (net (code "155") (name "unconnected-(U1B-PB13A-PadR8)") (class "Default")
      (node (ref "U1") (pin "R8") (pinfunction "PB13A_R8") (pintype "passive"))
    )
    (net (code "156") (name "unconnected-(U1B-PB13B-PadP8)") (class "Default")
      (node (ref "U1") (pin "P8") (pinfunction "PB13B_P8") (pintype "passive"))
    )
    (net (code "157") (name "unconnected-(U1B-PB15A-PadN8)") (class "Default")
      (node (ref "U1") (pin "N8") (pinfunction "PB15A_N8") (pintype "passive"))
    )
    (net (code "158") (name "unconnected-(U1B-PB18A-PadM9)") (class "Default")
      (node (ref "U1") (pin "M9") (pinfunction "PB18A_M9") (pintype "passive"))
    )
    (net (code "159") (name "unconnected-(U1B-PL17C-PadJ4)") (class "Default")
      (node (ref "U1") (pin "J4") (pinfunction "PL17C_J4") (pintype "passive"))
    )
    (net (code "160") (name "unconnected-(U1B-PL17D-PadJ5)") (class "Default")
      (node (ref "U1") (pin "J5") (pinfunction "PL17D_J5") (pintype "passive"))
    )
    (net (code "161") (name "unconnected-(U1B-PL20C-PadJ3)") (class "Default")
      (node (ref "U1") (pin "J3") (pinfunction "PL20C_J3") (pintype "passive"))
    )
    (net (code "162") (name "unconnected-(U1B-PL20D-PadK3)") (class "Default")
      (node (ref "U1") (pin "K3") (pinfunction "PL20D_K3") (pintype "passive"))
    )
    (net (code "163") (name "unconnected-(U1B-PL26A-PadL1)") (class "Default")
      (node (ref "U1") (pin "L1") (pinfunction "PL26A_L1") (pintype "passive"))
    )
    (net (code "164") (name "unconnected-(U1B-PL26B-PadL2)") (class "Default")
      (node (ref "U1") (pin "L2") (pinfunction "PL26B_L2") (pintype "passive"))
    )
    (net (code "165") (name "unconnected-(U1B-PL26D-PadM2)") (class "Default")
      (node (ref "U1") (pin "M2") (pinfunction "PL26D_M2") (pintype "passive"))
    )
    (net (code "166") (name "unconnected-(U1B-PL29A-PadK4)") (class "Default")
      (node (ref "U1") (pin "K4") (pinfunction "PL29A_K4") (pintype "passive"))
    )
    (net (code "167") (name "unconnected-(U1B-PL29B-PadK5)") (class "Default")
      (node (ref "U1") (pin "K5") (pinfunction "PL29B_K5") (pintype "passive"))
    )
    (net (code "168") (name "unconnected-(U1B-PL29C-PadL4)") (class "Default")
      (node (ref "U1") (pin "L4") (pinfunction "PL29C_L4") (pintype "passive"))
    )
    (net (code "169") (name "unconnected-(U1B-PL29D-PadL5)") (class "Default")
      (node (ref "U1") (pin "L5") (pinfunction "PL29D_L5") (pintype "passive"))
    )
    (net (code "170") (name "unconnected-(U1B-PL32A-PadN1)") (class "Default")
      (node (ref "U1") (pin "N1") (pinfunction "PL32A_N1") (pintype "passive"))
    )
    (net (code "171") (name "unconnected-(U1B-PL32B-PadP2)") (class "Default")
      (node (ref "U1") (pin "P2") (pinfunction "PL32B_P2") (pintype "passive"))
    )
    (net (code "172") (name "unconnected-(U1B-PL32C-PadL3)") (class "Default")
      (node (ref "U1") (pin "L3") (pinfunction "PL32C_L3") (pintype "passive"))
    )
    (net (code "173") (name "unconnected-(U1B-PL32D-PadM3)") (class "Default")
      (node (ref "U1") (pin "M3") (pinfunction "PL32D_M3") (pintype "passive"))
    )
    (net (code "174") (name "unconnected-(U1B-PL35A-PadP1)") (class "Default")
      (node (ref "U1") (pin "P1") (pinfunction "PL35A_P1") (pintype "passive"))
    )
    (net (code "175") (name "unconnected-(U1B-PL35C-PadM4)") (class "Default")
      (node (ref "U1") (pin "M4") (pinfunction "PL35C_M4") (pintype "passive"))
    )
    (net (code "176") (name "unconnected-(U1B-PL35D-PadN3)") (class "Default")
      (node (ref "U1") (pin "N3") (pinfunction "PL35D_N3") (pintype "passive"))
    )
    (net (code "177") (name "unconnected-(U1B-PL38A-PadN4)") (class "Default")
      (node (ref "U1") (pin "N4") (pinfunction "PL38A_N4") (pintype "passive"))
    )
    (net (code "178") (name "unconnected-(U1B-PL38B-PadP3)") (class "Default")
      (node (ref "U1") (pin "P3") (pinfunction "PL38B_P3") (pintype "passive"))
    )
    (net (code "179") (name "unconnected-(U1B-PL38C-PadR2)") (class "Default")
      (node (ref "U1") (pin "R2") (pinfunction "PL38C_R2") (pintype "passive"))
    )
    (net (code "180") (name "unconnected-(U1B-PL41A-PadP4)") (class "Default")
      (node (ref "U1") (pin "P4") (pinfunction "PL41A_P4") (pintype "passive"))
    )
    (net (code "181") (name "unconnected-(U1B-PL41B-PadR3)") (class "Default")
      (node (ref "U1") (pin "R3") (pinfunction "PL41B_R3") (pintype "passive"))
    )
    (net (code "182") (name "unconnected-(U1B-PL41C-PadR4)") (class "Default")
      (node (ref "U1") (pin "R4") (pinfunction "PL41C_R4") (pintype "passive"))
    )
    (net (code "183") (name "unconnected-(U1B-PL44A-PadR5)") (class "Default")
      (node (ref "U1") (pin "R5") (pinfunction "PL44A_R5") (pintype "passive"))
    )
    (net (code "184") (name "unconnected-(U1B-PL44C-PadM5)") (class "Default")
      (node (ref "U1") (pin "M5") (pinfunction "PL44C_M5") (pintype "passive"))
    )
    (net (code "185") (name "unconnected-(U1B-PL44D-PadN5)") (class "Default")
      (node (ref "U1") (pin "N5") (pinfunction "PL44D_N5") (pintype "passive"))
    )
    (net (code "186") (name "unconnected-(U1B-PL47A-PadM6)") (class "Default")
      (node (ref "U1") (pin "M6") (pinfunction "PL47A_M6") (pintype "passive"))
    )
    (net (code "187") (name "unconnected-(U1B-PL47B-PadN6)") (class "Default")
      (node (ref "U1") (pin "N6") (pinfunction "PL47B_N6") (pintype "passive"))
    )
    (net (code "188") (name "unconnected-(U1B-PL47C-PadP6)") (class "Default")
      (node (ref "U1") (pin "P6") (pinfunction "PL47C_P6") (pintype "passive"))
    )
    (net (code "189") (name "unconnected-(U1B-PL47D-PadP5)") (class "Default")
      (node (ref "U1") (pin "P5") (pinfunction "PL47D_P5") (pintype "passive"))
    )
    (net (code "190") (name "unconnected-(U1B-PR17C-PadJ13)") (class "Default")
      (node (ref "U1") (pin "J13") (pinfunction "PR17C_J13") (pintype "passive"))
    )
    (net (code "191") (name "unconnected-(U1B-PR17D-PadJ12)") (class "Default")
      (node (ref "U1") (pin "J12") (pinfunction "PR17D_J12") (pintype "passive"))
    )
    (net (code "192") (name "unconnected-(U1B-PR20D-PadK14)") (class "Default")
      (node (ref "U1") (pin "K14") (pinfunction "PR20D_K14") (pintype "passive"))
    )
    (net (code "193") (name "unconnected-(U1B-PR23D-PadK15)") (class "Default")
      (node (ref "U1") (pin "K15") (pinfunction "PR23D_K15") (pintype "passive"))
    )
    (net (code "194") (name "unconnected-(U1B-PR26A-PadL16)") (class "Default")
      (node (ref "U1") (pin "L16") (pinfunction "PR26A_L16") (pintype "passive"))
    )
    (net (code "195") (name "unconnected-(U1B-PR29A-PadK13)") (class "Default")
      (node (ref "U1") (pin "K13") (pinfunction "PR29A_K13") (pintype "passive"))
    )
    (net (code "196") (name "unconnected-(U1B-PR29C-PadL13)") (class "Default")
      (node (ref "U1") (pin "L13") (pinfunction "PR29C_L13") (pintype "passive"))
    )
    (net (code "197") (name "unconnected-(U1B-PR32A-PadN16)") (class "Default")
      (node (ref "U1") (pin "N16") (pinfunction "PR32A_N16") (pintype "passive"))
    )
    (net (code "198") (name "unconnected-(U1B-PR32B-PadP15)") (class "Default")
      (node (ref "U1") (pin "P15") (pinfunction "PR32B_P15") (pintype "passive"))
    )
    (net (code "199") (name "unconnected-(U1B-PR32C-PadL14)") (class "Default")
      (node (ref "U1") (pin "L14") (pinfunction "PR32C_L14") (pintype "passive"))
    )
    (net (code "200") (name "unconnected-(U1B-PR35C-PadM13)") (class "Default")
      (node (ref "U1") (pin "M13") (pinfunction "PR35C_M13") (pintype "passive"))
    )
    (net (code "201") (name "unconnected-(U1B-PR35D-PadN14)") (class "Default")
      (node (ref "U1") (pin "N14") (pinfunction "PR35D_N14") (pintype "passive"))
    )
    (net (code "202") (name "unconnected-(U1B-PR38B-PadP14)") (class "Default")
      (node (ref "U1") (pin "P14") (pinfunction "PR38B_P14") (pintype "passive"))
    )
    (net (code "203") (name "unconnected-(U1B-PR41A-PadP13)") (class "Default")
      (node (ref "U1") (pin "P13") (pinfunction "PR41A_P13") (pintype "passive"))
    )
    (net (code "204") (name "unconnected-(U1B-PR41B-PadR14)") (class "Default")
      (node (ref "U1") (pin "R14") (pinfunction "PR41B_R14") (pintype "passive"))
    )
    (net (code "205") (name "unconnected-(U1B-PR44A-PadR12)") (class "Default")
      (node (ref "U1") (pin "R12") (pinfunction "PR44A_R12") (pintype "passive"))
    )
    (net (code "206") (name "unconnected-(U1B-PR44B-PadT13)") (class "Default")
      (node (ref "U1") (pin "T13") (pinfunction "PR44B_T13") (pintype "passive"))
    )
    (net (code "207") (name "unconnected-(U1B-PR44C-PadM12)") (class "Default")
      (node (ref "U1") (pin "M12") (pinfunction "PR44C_M12") (pintype "passive"))
    )
    (net (code "208") (name "unconnected-(U1B-PR44D-PadN12)") (class "Default")
      (node (ref "U1") (pin "N12") (pinfunction "PR44D_N12") (pintype "passive"))
    )
    (net (code "209") (name "unconnected-(U1B-PR47A-PadM11)") (class "Default")
      (node (ref "U1") (pin "M11") (pinfunction "PR47A_M11") (pintype "passive"))
    )
    (net (code "210") (name "unconnected-(U1B-PR47B-PadN11)") (class "Default")
      (node (ref "U1") (pin "N11") (pinfunction "PR47B_N11") (pintype "passive"))
    )
    (net (code "211") (name "unconnected-(U1B-PR47C-PadP11)") (class "Default")
      (node (ref "U1") (pin "P11") (pinfunction "PR47C_P11") (pintype "passive"))
    )
    (net (code "212") (name "unconnected-(U1B-PR47D-PadP12)") (class "Default")
      (node (ref "U1") (pin "P12") (pinfunction "PR47D_P12") (pintype "passive"))
    )
  )
)
